# Source_VDDP.net
KiCad netlist of a schematic drawn in Altium Designer
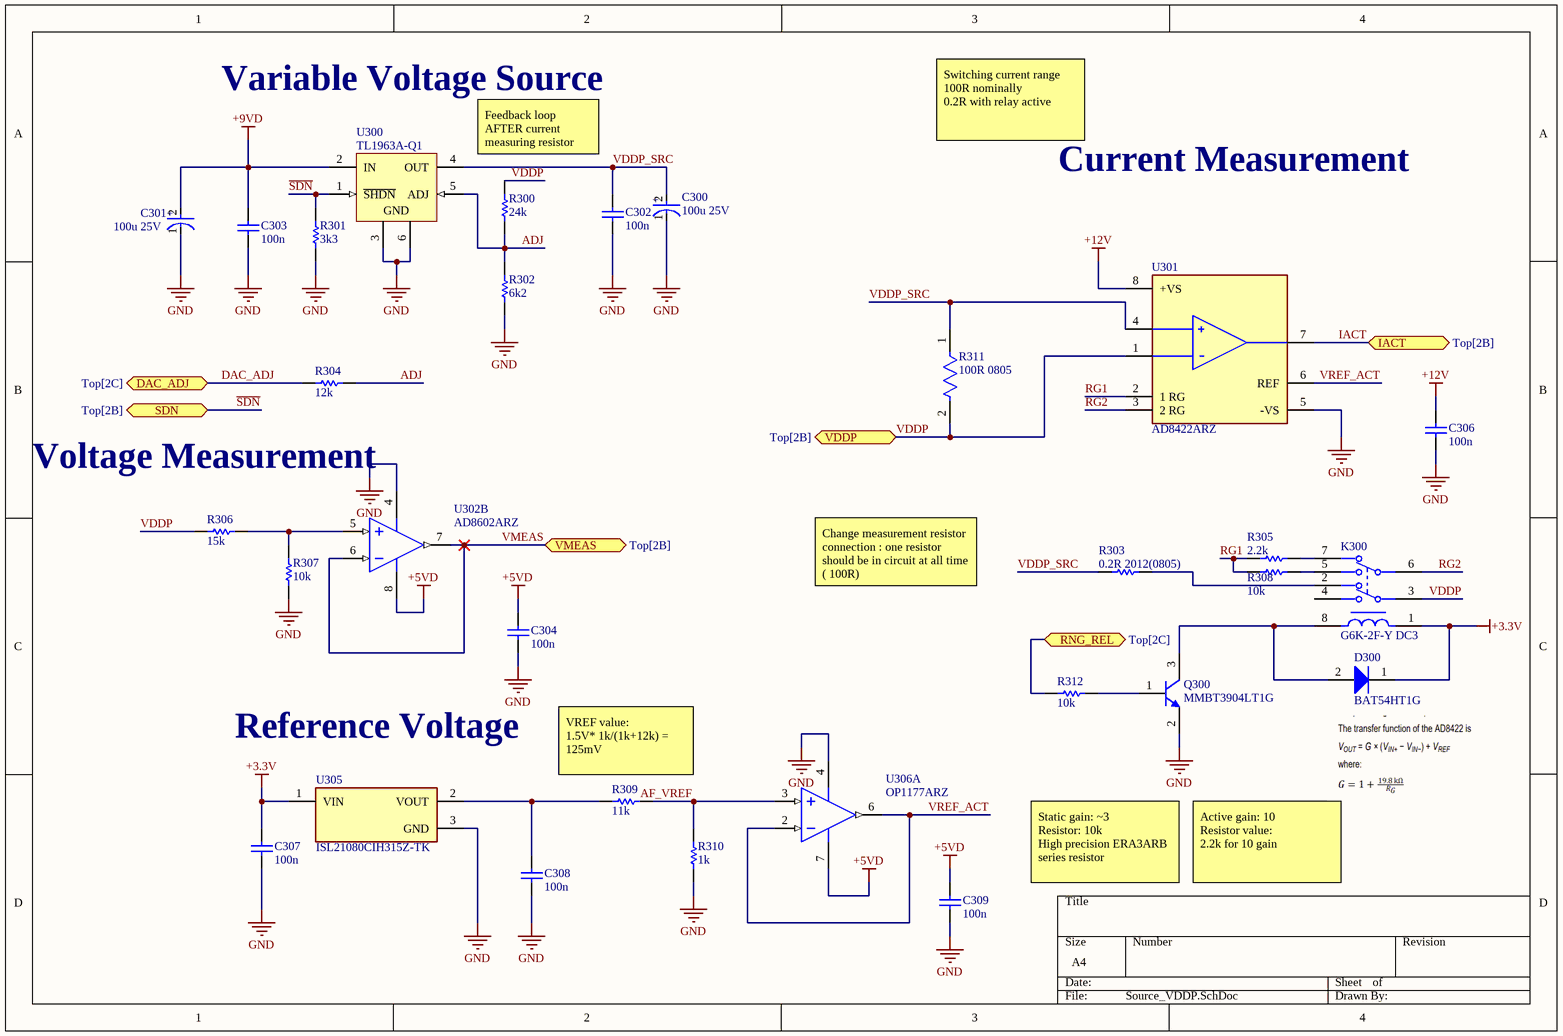
[diagram p0: Source_VDDP.SchDoc]

(export (version "E")
  (design (tool "Eeschema 10.0.6"))
  (components
    (comp (ref "C300")
      (value "100u 25V")
      (footprint "FP-T491X107K025AT-MFG")
      (description "CAP TANT 100UF 10% 25V 2917")
      (fields (field (name "TOLERANCE") "10%") (field (name "VOLTAGE") "25V"))
      (libsource (lib "Altium Content Vault") (part "cf48714ba7e38822c1575c7ec0b6d1f"))
    )
    (comp (ref "C301")
      (value "100u 25V")
      (footprint "FP-T491X107K025AT-MFG")
      (description "CAP TANT 100UF 10% 25V 2917")
      (fields (field (name "TOLERANCE") "10%") (field (name "VOLTAGE") "25V"))
      (libsource (lib "Altium Content Vault") (part "cf48714ba7e38822c1575c7ec0b6d1f"))
    )
    (comp (ref "C302")
      (value "100n")
      (footprint "SAMS-C0603-2_M")
      (description "Multi-layer Ceramic Capacitor, -55 to 125 degC, 2-Pin SMD (0603), RoHS, Tape and Reel")
      (fields (field (name "MANUFACTURER") "Samsung Electro-Mechanics"))
      (libsource (lib "Altium Content Vault") (part "CAP-NP-2"))
    )
    (comp (ref "C303")
      (value "100n")
      (footprint "SAMS-C0603-2_M")
      (description "Multi-layer Ceramic Capacitor, -55 to 125 degC, 2-Pin SMD (0603), RoHS, Tape and Reel")
      (fields (field (name "MANUFACTURER") "Samsung Electro-Mechanics"))
      (libsource (lib "Altium Content Vault") (part "CAP-NP-2"))
    )
    (comp (ref "C304")
      (value "100n")
      (footprint "SAMS-C0603-2_M")
      (description "Multi-layer Ceramic Capacitor, -55 to 125 degC, 2-Pin SMD (0603), RoHS, Tape and Reel")
      (fields (field (name "MANUFACTURER") "Samsung Electro-Mechanics"))
      (libsource (lib "Altium Content Vault") (part "CAP-NP-2"))
    )
    (comp (ref "C306")
      (value "100n")
      (footprint "SAMS-C0603-2_M")
      (description "Multi-layer Ceramic Capacitor, -55 to 125 degC, 2-Pin SMD (0603), RoHS, Tape and Reel")
      (fields (field (name "MANUFACTURER") "Samsung Electro-Mechanics"))
      (libsource (lib "Altium Content Vault") (part "CAP-NP-2"))
    )
    (comp (ref "C307")
      (value "100n")
      (footprint "SAMS-C0603-2_M")
      (description "Multi-layer Ceramic Capacitor, -55 to 125 degC, 2-Pin SMD (0603), RoHS, Tape and Reel")
      (fields (field (name "MANUFACTURER") "Samsung Electro-Mechanics"))
      (libsource (lib "Altium Content Vault") (part "CAP-NP-2"))
    )
    (comp (ref "C308")
      (value "100n")
      (footprint "SAMS-C0603-2_M")
      (description "Multi-layer Ceramic Capacitor, -55 to 125 degC, 2-Pin SMD (0603), RoHS, Tape and Reel")
      (fields (field (name "MANUFACTURER") "Samsung Electro-Mechanics"))
      (libsource (lib "Altium Content Vault") (part "CAP-NP-2"))
    )
    (comp (ref "C309")
      (value "100n")
      (footprint "SAMS-C0603-2_M")
      (description "Multi-layer Ceramic Capacitor, -55 to 125 degC, 2-Pin SMD (0603), RoHS, Tape and Reel")
      (fields (field (name "MANUFACTURER") "Samsung Electro-Mechanics"))
      (libsource (lib "Altium Content Vault") (part "CAP-NP-2"))
    )
    (comp (ref "D300")
      (value "BAT54HT1G")
      (footprint "ONSC-SOD-323-2-477-02_V")
      (description "Schottky Barrier Diode, 2-Pin SOD-323, Pb-Free, Tape and Reel")
      (fields (field (name "MANUFACTURER") "On Semiconductor"))
      (libsource (lib "Altium Content Vault") (part "ONSC-D-K1A2-2"))
    )
    (comp (ref "K300")
      (value "G6K-2F-Y DC3")
      (footprint "FP-G6K-2F-Y_DC3-MFG")
      (description "RELAY TELECOM DPDT 1A 3VDC")
      (fields
        (field (name "MANUFACTURER") "Omron")
        (field (name "OCTOPART") "https://octopart.com/g6k-2f-y-dc3-omron-694063")
      )
      (libsource (lib "Altium Content Vault") (part "58c38101009d5ebbf9054263c5b66d6"))
    )
    (comp (ref "Q300")
      (value "MMBT3904LT1G")
      (footprint "ONSC-SOT-23-3-318-08_V")
      (description "General Purpose Transistor, NPN Silicon, 3-Pin SOT-23, Pb-Free, Tape and Reel")
      (fields (field (name "MANUFACTURER") "On Semiconductor"))
      (libsource (lib "Altium Content Vault") (part "ONSC-NPN-B1E2C3-3"))
    )
    (comp (ref "R300")
      (value "24k")
      (footprint "RESC1608X55X30ML15T15")
      (fields (field (name "PART NUMBER") "ERJ-3EKF2402V") (field (name "MANUFACTURER") "Panasonic"))
      (libsource (lib "Altium Content Vault") (part "RES"))
    )
    (comp (ref "R301")
      (value "3k3")
      (footprint "RESC1609X55X30ML15T15")
      (description "Chip Resistors, 3.3 KOhm, +/- 1%, 0.1 W, 0603 (1608 Metric), -55 to 155 degC, RoHS, Tape and Reel")
      (fields (field (name "MANUFACTURER") "Panasonic") (field (name "TOLERANCE") "1%"))
      (libsource (lib "Altium Content Vault") (part "RES-2"))
    )
    (comp (ref "R302")
      (value "6k2")
      (footprint "RESC1608X55X30ML15T15")
      (fields (field (name "MANUFACTURER") "Panasonic") (field (name "PART NUMBER") "ERJ-3EKF6200V"))
      (libsource (lib "Altium Content Vault") (part "RES"))
    )
    (comp (ref "R303")
      (value "0.2R 2012(0805)")
      (footprint "RESC2013X46X38ML25T25")
      (fields (field (name "PART NUMBER") "WSL0805R2000FEA") (field (name "MANUFACTURER") "Vishay Dale"))
      (libsource (lib "Altium Content Vault") (part "RES"))
    )
    (comp (ref "R304")
      (value "12k")
      (footprint "RESC1608X55X30ML15T15")
      (fields (field (name "PART NUMBER") "ERJ-3GEYJ201V") (field (name "MANUFACTURER") "Panasonic"))
      (libsource (lib "Altium Content Vault") (part "RES"))
    )
    (comp (ref "R305")
      (value "2.2k")
      (footprint "RESC1609X55X30ML15T15")
      (description "Chip Resistor, 1.2 KOhm, +/- 1%, 0.1 W, -55 to 155 degC, 0603 (1608 Metric), RoHS, Tape and Reel")
      (fields (field (name "MANUFACTURER") "Panasonic") (field (name "TOLERANCE") "1%"))
      (libsource (lib "Altium Content Vault") (part "RES-2"))
    )
    (comp (ref "R306")
      (value "15k")
      (footprint "RESC1608X55X30ML15T15")
      (fields (field (name "PART NUMBER") "ERJ-3EKF3602V") (field (name "MANUFACTURER") "Panasonic"))
      (libsource (lib "Altium Content Vault") (part "RES"))
    )
    (comp (ref "R307")
      (value "10k")
      (footprint "RESC1608X55X30ML15T15")
      (fields (field (name "PART NUMBER") "ERJ-3GEYJ303V") (field (name "MANUFACTURER") "Panasonic"))
      (libsource (lib "Altium Content Vault") (part "RES"))
    )
    (comp (ref "R308")
      (value "10k")
      (footprint "RESC1608X55X30ML15T15")
      (description "Chip Resistor, 22 Ohm, +/- 1%, 0.1 W, -55 to 155 degC, 0603 (1608 Metric), RoHS, Tape and Reel")
      (libsource (lib "Altium Content Vault") (part "RES-2"))
    )
    (comp (ref "R309")
      (value "11k")
      (footprint "RESC1608X55X30ML15T15")
      (fields (field (name "PART NUMBER") "ERJ-3EKF1102V") (field (name "MANUFACTURER") "Panasonic"))
      (libsource (lib "Altium Content Vault") (part "RES"))
    )
    (comp (ref "R310")
      (value "1k")
      (footprint "RESC1608X55X30ML15T15")
      (fields (field (name "PART NUMBER") "ERJ-3EKF1001V") (field (name "MANUFACTURER") "Panasonic"))
      (libsource (lib "Altium Content Vault") (part "RES"))
    )
    (comp (ref "R311")
      (value "100R 0805")
      (footprint "FP-CRCW0805-e3-MFG")
      (description "RES Thick Film, 100Ω, 1%, 0.125W, 100ppm/°C, 0805")
      (fields (field (name "TOLERANCE") "1%"))
      (libsource (lib "Altium Content Vault") (part "1029c3af85768c4190bb7ad29bc67b5"))
    )
    (comp (ref "R312")
      (value "10k")
      (footprint "RESC1608X55X30ML15T15")
      (fields (field (name "PART NUMBER") "ERJ-3GEYJ303V") (field (name "MANUFACTURER") "Panasonic"))
      (libsource (lib "Altium Content Vault") (part "RES"))
    )
    (comp (ref "U300")
      (value "TL1963A-Q1")
      (footprint "KTT0005A_M")
      (fields (field (name "PARTNUMBER") "TL1963AKTTR") (field (name "MANUFACTURER") "Texas Instruments"))
      (libsource (lib "Altium Content Vault") (part "TI-TPS7A4501_TL1963A-6"))
    )
    (comp (ref "U301")
      (value "AD8422ARZ")
      (footprint "FP-R-8-IPC_A")
      (description "IC INST AMP 1 CIRCUIT 8SOIC")
      (libsource (lib "Altium Content Vault") (part "c8ce1a14eba5bbcc74e575812f36567"))
    )
    (comp (ref "U302")
      (value "AD8602ARZ")
      (footprint "ADI-R-8_N")
      (fields (field (name "GENERIC PART NUMBER") "AD8602") (field (name "MANUFACTURER") "Analog Devices"))
      (libsource (lib "Altium Content Vault") (part "ADI-OP29X-R-8"))
    )
    (comp (ref "U305")
      (value "ISL21080CIH315Z-TK")
      (footprint "FP-P3_064A-IPC_A")
      (description "IC VREF SERIES 0.5% SOT23-3")
      (libsource (lib "Altium Content Vault") (part "962e5ce8f08f2276f18e857990e14fe"))
    )
    (comp (ref "U306")
      (value "OP1177ARZ")
      (footprint "ADI-R-8_M")
      (fields (field (name "MANUFACTURER") "Analog Devices") (field (name "GENERIC PART NUMBER") "OP1177"))
      (libsource (lib "Altium Content Vault") (part "ADI-AD_ADA_OPXXXX-X-8"))
    )
  )
  (nets
    (net (code "1") (name "+3.3V") (class "Default")
      (node (ref "C307") (pin "2") (pinfunction "2_2") (pintype "passive"))
      (node (ref "D300") (pin "1") (pinfunction "K_1") (pintype "passive"))
      (node (ref "K300") (pin "1") (pinfunction "1_1") (pintype "passive"))
      (node (ref "U305") (pin "1") (pinfunction "VIN_1") (pintype "power_in"))
    )
    (net (code "2") (name "+5VD") (class "Default")
      (node (ref "C304") (pin "2") (pinfunction "2_2") (pintype "passive"))
      (node (ref "C309") (pin "2") (pinfunction "2_2") (pintype "passive"))
      (node (ref "U302") (pin "8") (pinfunction "+V_8") (pintype "power_in"))
      (node (ref "U306") (pin "7") (pinfunction "+V_7") (pintype "power_in"))
    )
    (net (code "3") (name "+9VD") (class "Default")
      (node (ref "C301") (pin "2") (pinfunction "A_2") (pintype "passive"))
      (node (ref "C303") (pin "2") (pinfunction "2_2") (pintype "passive"))
      (node (ref "U300") (pin "2") (pinfunction "IN_2") (pintype "power_in"))
    )
    (net (code "4") (name "+12V") (class "Default")
      (node (ref "C306") (pin "2") (pinfunction "2_2") (pintype "passive"))
      (node (ref "U301") (pin "8") (pinfunction "+VS_8") (pintype "power_in"))
    )
    (net (code "5") (name "/ADJ") (class "Default")
      (node (ref "R300") (pin "1") (pinfunction "1_1") (pintype "passive"))
      (node (ref "R302") (pin "2") (pinfunction "2_2") (pintype "passive"))
      (node (ref "R304") (pin "2") (pinfunction "2_2") (pintype "passive"))
      (node (ref "U300") (pin "5") (pinfunction "ADJ_5") (pintype "input"))
    )
    (net (code "6") (name "/AF_VREF") (class "Default")
      (node (ref "R309") (pin "1") (pinfunction "1_1") (pintype "passive"))
      (node (ref "R310") (pin "2") (pinfunction "2_2") (pintype "passive"))
      (node (ref "U306") (pin "3") (pinfunction "+IN_3") (pintype "input"))
    )
    (net (code "7") (name "/DAC_ADJ") (class "Default")
      (node (ref "R304") (pin "1") (pinfunction "1_1") (pintype "passive"))
    )
    (net (code "8") (name "/IACT") (class "Default")
      (node (ref "U301") (pin "7") (pinfunction "VOUT_7") (pintype "passive"))
    )
    (net (code "9") (name "/RG1") (class "Default")
      (node (ref "R305") (pin "1") (pinfunction "1_1") (pintype "passive"))
      (node (ref "R308") (pin "1") (pinfunction "1_1") (pintype "passive"))
      (node (ref "U301") (pin "2") (pinfunction "1_RG_2") (pintype "passive"))
    )
    (net (code "10") (name "/RG2") (class "Default")
      (node (ref "K300") (pin "6") (pinfunction "6_6") (pintype "passive"))
      (node (ref "U301") (pin "3") (pinfunction "2_RG_3") (pintype "passive"))
    )
    (net (code "11") (name "/RNG_REL") (class "Default")
      (node (ref "R312") (pin "2") (pinfunction "2_2") (pintype "passive"))
    )
    (net (code "12") (name "/VDDP") (class "Default")
      (node (ref "K300") (pin "3") (pinfunction "3_3") (pintype "passive"))
      (node (ref "R300") (pin "2") (pinfunction "2_2") (pintype "passive"))
      (node (ref "R306") (pin "1") (pinfunction "1_1") (pintype "passive"))
      (node (ref "R311") (pin "2") (pinfunction "2_2") (pintype "passive"))
      (node (ref "U301") (pin "1") (pinfunction "-IN_1") (pintype "tri_state"))
    )
    (net (code "13") (name "/VDDP_SRC") (class "Default")
      (node (ref "C300") (pin "2") (pinfunction "A_2") (pintype "passive"))
      (node (ref "C302") (pin "2") (pinfunction "2_2") (pintype "passive"))
      (node (ref "R303") (pin "2") (pinfunction "2_2") (pintype "passive"))
      (node (ref "R311") (pin "1") (pinfunction "1_1") (pintype "passive"))
      (node (ref "U300") (pin "4") (pinfunction "OUT_4") (pintype "power_in"))
      (node (ref "U301") (pin "4") (pinfunction "+IN_4") (pintype "tri_state"))
    )
    (net (code "14") (name "/VMEAS") (class "Default")
      (node (ref "U302") (pin "6") (pinfunction "-IN_B_6") (pintype "input"))
      (node (ref "U302") (pin "7") (pinfunction "OUT_B_7") (pintype "output"))
    )
    (net (code "15") (name "/VREF_ACT") (class "Default")
      (node (ref "U301") (pin "6") (pinfunction "REF_6") (pintype "passive"))
      (node (ref "U306") (pin "2") (pinfunction "-IN_2") (pintype "input"))
      (node (ref "U306") (pin "6") (pinfunction "OUT_6") (pintype "output"))
    )
    (net (code "16") (name "/~{SDN}") (class "Default")
      (node (ref "R301") (pin "2") (pinfunction "2_2") (pintype "passive"))
      (node (ref "U300") (pin "1") (pinfunction "~{SHDN}_1") (pintype "input"))
    )
    (net (code "17") (name "GND") (class "Default")
      (node (ref "C300") (pin "1") (pinfunction "C_1") (pintype "passive"))
      (node (ref "C301") (pin "1") (pinfunction "C_1") (pintype "passive"))
      (node (ref "C302") (pin "1") (pinfunction "1_1") (pintype "passive"))
      (node (ref "C303") (pin "1") (pinfunction "1_1") (pintype "passive"))
      (node (ref "C304") (pin "1") (pinfunction "1_1") (pintype "passive"))
      (node (ref "C306") (pin "1") (pinfunction "1_1") (pintype "passive"))
      (node (ref "C307") (pin "1") (pinfunction "1_1") (pintype "passive"))
      (node (ref "C308") (pin "1") (pinfunction "1_1") (pintype "passive"))
      (node (ref "C309") (pin "1") (pinfunction "1_1") (pintype "passive"))
      (node (ref "Q300") (pin "2") (pinfunction "E_2") (pintype "passive"))
      (node (ref "R301") (pin "1") (pinfunction "1_1") (pintype "passive"))
      (node (ref "R302") (pin "1") (pinfunction "1_1") (pintype "passive"))
      (node (ref "R307") (pin "1") (pinfunction "1_1") (pintype "passive"))
      (node (ref "R310") (pin "1") (pinfunction "1_1") (pintype "passive"))
      (node (ref "U300") (pin "3") (pinfunction "GND_3") (pintype "power_in"))
      (node (ref "U300") (pin "6") (pinfunction "GND_6") (pintype "power_in"))
      (node (ref "U301") (pin "5") (pinfunction "-VS_5") (pintype "power_in"))
      (node (ref "U302") (pin "4") (pinfunction "-V_4") (pintype "power_in"))
      (node (ref "U305") (pin "3") (pinfunction "GND_3") (pintype "power_in"))
      (node (ref "U306") (pin "4") (pinfunction "-V_4") (pintype "power_in"))
    )
    (net (code "18") (name "Net-(D300-A)") (class "Default")
      (node (ref "D300") (pin "2") (pinfunction "A_2") (pintype "passive"))
      (node (ref "K300") (pin "8") (pinfunction "8_8") (pintype "passive"))
      (node (ref "Q300") (pin "3") (pinfunction "C_3") (pintype "passive"))
    )
    (net (code "19") (name "Net-(K300-Pad2)") (class "Default")
      (node (ref "K300") (pin "2") (pinfunction "2_2") (pintype "passive"))
      (node (ref "R303") (pin "1") (pinfunction "1_1") (pintype "passive"))
    )
    (net (code "20") (name "Net-(K300-Pad5)") (class "Default")
      (node (ref "K300") (pin "5") (pinfunction "5_5") (pintype "passive"))
      (node (ref "R308") (pin "2") (pinfunction "2_2") (pintype "passive"))
    )
    (net (code "21") (name "Net-(K300-Pad7)") (class "Default")
      (node (ref "K300") (pin "7") (pinfunction "7_7") (pintype "passive"))
      (node (ref "R305") (pin "2") (pinfunction "2_2") (pintype "passive"))
    )
    (net (code "22") (name "Net-(Q300-B)") (class "Default")
      (node (ref "Q300") (pin "1") (pinfunction "B_1") (pintype "passive"))
      (node (ref "R312") (pin "1") (pinfunction "1_1") (pintype "passive"))
    )
    (net (code "23") (name "Net-(U302B-+IN_B)") (class "Default")
      (node (ref "R306") (pin "2") (pinfunction "2_2") (pintype "passive"))
      (node (ref "R307") (pin "2") (pinfunction "2_2") (pintype "passive"))
      (node (ref "U302") (pin "5") (pinfunction "+IN_B_5") (pintype "input"))
    )
    (net (code "24") (name "Net-(U305-VOUT)") (class "Default")
      (node (ref "C308") (pin "2") (pinfunction "2_2") (pintype "passive"))
      (node (ref "R309") (pin "2") (pinfunction "2_2") (pintype "passive"))
      (node (ref "U305") (pin "2") (pinfunction "VOUT_2") (pintype "power_in"))
    )
    (net (code "25") (name "unconnected-(K300-Pad4)") (class "Default")
      (node (ref "K300") (pin "4") (pinfunction "4_4") (pintype "passive"))
    )
  )
)
